# irRemote.net
KiCad netlist of a schematic drawn in EAGLE
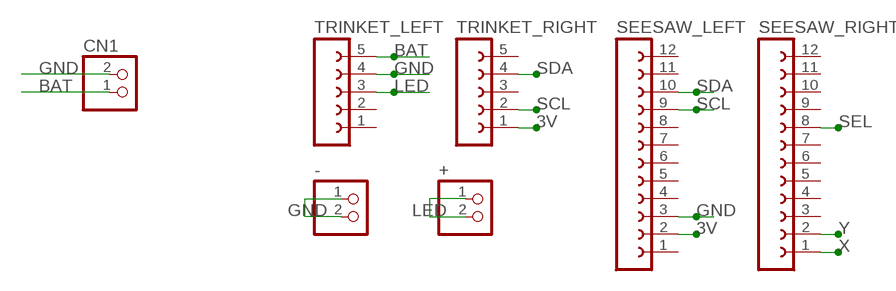
[diagram p0: schematic, sheet 1]
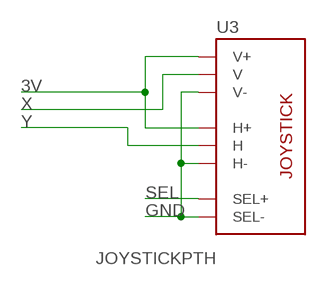
[diagram p1: schematic, sheet 2]

(export (version "E")
  (design (tool "Eeschema 10.0.6"))
  (components
    (comp (ref "U3")
      (value "JOYSTICKPTH")
      (footprint "eagle-import:JOYSTICK")
      (libsource (lib "eagle-import") (part "JOYSTICKPTH"))
    )
    (comp (ref "+")
      (value "PINHD-1X2")
      (footprint "eagle-import:1X02")
      (libsource (lib "eagle-import") (part "PINHD-1X2"))
    )
    (comp (ref "-")
      (value "PINHD-1X2")
      (footprint "eagle-import:1X02")
      (libsource (lib "eagle-import") (part "PINHD-1X2"))
    )
    (comp (ref "CN1")
      (value "JST_2PIN-SMT-RA")
      (footprint "eagle-import:JST-PH-2-SMT-RA")
      (libsource (lib "eagle-import") (part "JST_2PIN-SMT-RA"))
    )
    (comp (ref "SEESAW_LEFT")
      (value "FE12-1")
      (footprint "eagle-import:FE12")
      (libsource (lib "eagle-import") (part "FE12-1"))
    )
    (comp (ref "SEESAW_RIGHT")
      (value "FE12-1")
      (footprint "eagle-import:FE12")
      (libsource (lib "eagle-import") (part "FE12-1"))
    )
    (comp (ref "TRINKET_LEFT")
      (value "FE05-1")
      (footprint "eagle-import:FE05-1")
      (libsource (lib "eagle-import") (part "FE05-1"))
    )
    (comp (ref "TRINKET_RIGHT")
      (value "FE05-1")
      (footprint "eagle-import:FE05-1")
      (libsource (lib "eagle-import") (part "FE05-1"))
    )
  )
  (nets
    (net (code "1") (name "3V") (class "Default")
      (node (ref "SEESAW_LEFT") (pin "2") (pinfunction "2_2") (pintype "passive"))
      (node (ref "TRINKET_RIGHT") (pin "1") (pinfunction "1_1") (pintype "passive"))
      (node (ref "U3") (pin "H1") (pinfunction "H+_H1") (pintype "bidirectional"))
      (node (ref "U3") (pin "V1") (pinfunction "V+_V1") (pintype "bidirectional"))
    )
    (net (code "2") (name "BAT") (class "Default")
      (node (ref "CN1") (pin "1") (pinfunction "2_1") (pintype "passive"))
      (node (ref "TRINKET_LEFT") (pin "5") (pinfunction "5_5") (pintype "passive"))
    )
    (net (code "3") (name "GND") (class "Default")
      (node (ref "-") (pin "1") (pinfunction "1_1") (pintype "passive"))
      (node (ref "-") (pin "2") (pinfunction "2_2") (pintype "passive"))
      (node (ref "CN1") (pin "2") (pinfunction "1_2") (pintype "passive"))
      (node (ref "SEESAW_LEFT") (pin "3") (pinfunction "3_3") (pintype "passive"))
      (node (ref "TRINKET_LEFT") (pin "4") (pinfunction "4_4") (pintype "passive"))
      (node (ref "U3") (pin "B2A") (pinfunction "SEL-_B2A") (pintype "bidirectional"))
      (node (ref "U3") (pin "H3") (pinfunction "H-_H3") (pintype "bidirectional"))
      (node (ref "U3") (pin "V3") (pinfunction "V-_V3") (pintype "bidirectional"))
    )
    (net (code "4") (name "LED") (class "Default")
      (node (ref "+") (pin "1") (pinfunction "1_1") (pintype "passive"))
      (node (ref "+") (pin "2") (pinfunction "2_2") (pintype "passive"))
      (node (ref "TRINKET_LEFT") (pin "3") (pinfunction "3_3") (pintype "passive"))
    )
    (net (code "5") (name "SCL") (class "Default")
      (node (ref "SEESAW_LEFT") (pin "9") (pinfunction "9_9") (pintype "passive"))
      (node (ref "TRINKET_RIGHT") (pin "2") (pinfunction "2_2") (pintype "passive"))
    )
    (net (code "6") (name "SDA") (class "Default")
      (node (ref "SEESAW_LEFT") (pin "10") (pinfunction "10_10") (pintype "passive"))
      (node (ref "TRINKET_RIGHT") (pin "4") (pinfunction "4_4") (pintype "passive"))
    )
    (net (code "7") (name "SEL") (class "Default")
      (node (ref "SEESAW_RIGHT") (pin "8") (pinfunction "8_8") (pintype "passive"))
      (node (ref "U3") (pin "B1A") (pinfunction "SEL+_B1A") (pintype "bidirectional"))
    )
    (net (code "8") (name "X") (class "Default")
      (node (ref "SEESAW_RIGHT") (pin "1") (pinfunction "1_1") (pintype "passive"))
      (node (ref "U3") (pin "V2") (pinfunction "V_V2") (pintype "bidirectional"))
    )
    (net (code "9") (name "Y") (class "Default")
      (node (ref "SEESAW_RIGHT") (pin "2") (pinfunction "2_2") (pintype "passive"))
      (node (ref "U3") (pin "H2") (pinfunction "H_H2") (pintype "bidirectional"))
    )
    (net (code "10") (name "unconnected-(SEESAW_LEFT-Pad1)") (class "Default")
      (node (ref "SEESAW_LEFT") (pin "1") (pinfunction "1_1") (pintype "passive"))
    )
    (net (code "11") (name "unconnected-(SEESAW_LEFT-Pad4)") (class "Default")
      (node (ref "SEESAW_LEFT") (pin "4") (pinfunction "4_4") (pintype "passive"))
    )
    (net (code "12") (name "unconnected-(SEESAW_LEFT-Pad5)") (class "Default")
      (node (ref "SEESAW_LEFT") (pin "5") (pinfunction "5_5") (pintype "passive"))
    )
    (net (code "13") (name "unconnected-(SEESAW_LEFT-Pad6)") (class "Default")
      (node (ref "SEESAW_LEFT") (pin "6") (pinfunction "6_6") (pintype "passive"))
    )
    (net (code "14") (name "unconnected-(SEESAW_LEFT-Pad7)") (class "Default")
      (node (ref "SEESAW_LEFT") (pin "7") (pinfunction "7_7") (pintype "passive"))
    )
    (net (code "15") (name "unconnected-(SEESAW_LEFT-Pad8)") (class "Default")
      (node (ref "SEESAW_LEFT") (pin "8") (pinfunction "8_8") (pintype "passive"))
    )
    (net (code "16") (name "unconnected-(SEESAW_LEFT-Pad11)") (class "Default")
      (node (ref "SEESAW_LEFT") (pin "11") (pinfunction "11_11") (pintype "passive"))
    )
    (net (code "17") (name "unconnected-(SEESAW_LEFT-Pad12)") (class "Default")
      (node (ref "SEESAW_LEFT") (pin "12") (pinfunction "12_12") (pintype "passive"))
    )
    (net (code "18") (name "unconnected-(SEESAW_RIGHT-Pad3)") (class "Default")
      (node (ref "SEESAW_RIGHT") (pin "3") (pinfunction "3_3") (pintype "passive"))
    )
    (net (code "19") (name "unconnected-(SEESAW_RIGHT-Pad4)") (class "Default")
      (node (ref "SEESAW_RIGHT") (pin "4") (pinfunction "4_4") (pintype "passive"))
    )
    (net (code "20") (name "unconnected-(SEESAW_RIGHT-Pad5)") (class "Default")
      (node (ref "SEESAW_RIGHT") (pin "5") (pinfunction "5_5") (pintype "passive"))
    )
    (net (code "21") (name "unconnected-(SEESAW_RIGHT-Pad6)") (class "Default")
      (node (ref "SEESAW_RIGHT") (pin "6") (pinfunction "6_6") (pintype "passive"))
    )
    (net (code "22") (name "unconnected-(SEESAW_RIGHT-Pad7)") (class "Default")
      (node (ref "SEESAW_RIGHT") (pin "7") (pinfunction "7_7") (pintype "passive"))
    )
    (net (code "23") (name "unconnected-(SEESAW_RIGHT-Pad9)") (class "Default")
      (node (ref "SEESAW_RIGHT") (pin "9") (pinfunction "9_9") (pintype "passive"))
    )
    (net (code "24") (name "unconnected-(SEESAW_RIGHT-Pad10)") (class "Default")
      (node (ref "SEESAW_RIGHT") (pin "10") (pinfunction "10_10") (pintype "passive"))
    )
    (net (code "25") (name "unconnected-(SEESAW_RIGHT-Pad11)") (class "Default")
      (node (ref "SEESAW_RIGHT") (pin "11") (pinfunction "11_11") (pintype "passive"))
    )
    (net (code "26") (name "unconnected-(SEESAW_RIGHT-Pad12)") (class "Default")
      (node (ref "SEESAW_RIGHT") (pin "12") (pinfunction "12_12") (pintype "passive"))
    )
    (net (code "27") (name "unconnected-(TRINKET_LEFT-Pad1)") (class "Default")
      (node (ref "TRINKET_LEFT") (pin "1") (pinfunction "1_1") (pintype "passive"))
    )
    (net (code "28") (name "unconnected-(TRINKET_LEFT-Pad2)") (class "Default")
      (node (ref "TRINKET_LEFT") (pin "2") (pinfunction "2_2") (pintype "passive"))
    )
    (net (code "29") (name "unconnected-(TRINKET_RIGHT-Pad3)") (class "Default")
      (node (ref "TRINKET_RIGHT") (pin "3") (pinfunction "3_3") (pintype "passive"))
    )
    (net (code "30") (name "unconnected-(TRINKET_RIGHT-Pad5)") (class "Default")
      (node (ref "TRINKET_RIGHT") (pin "5") (pinfunction "5_5") (pintype "passive"))
    )
  )
)
